# ps_3PS_detect.net
KiCad netlist of a schematic drawn in EAGLE
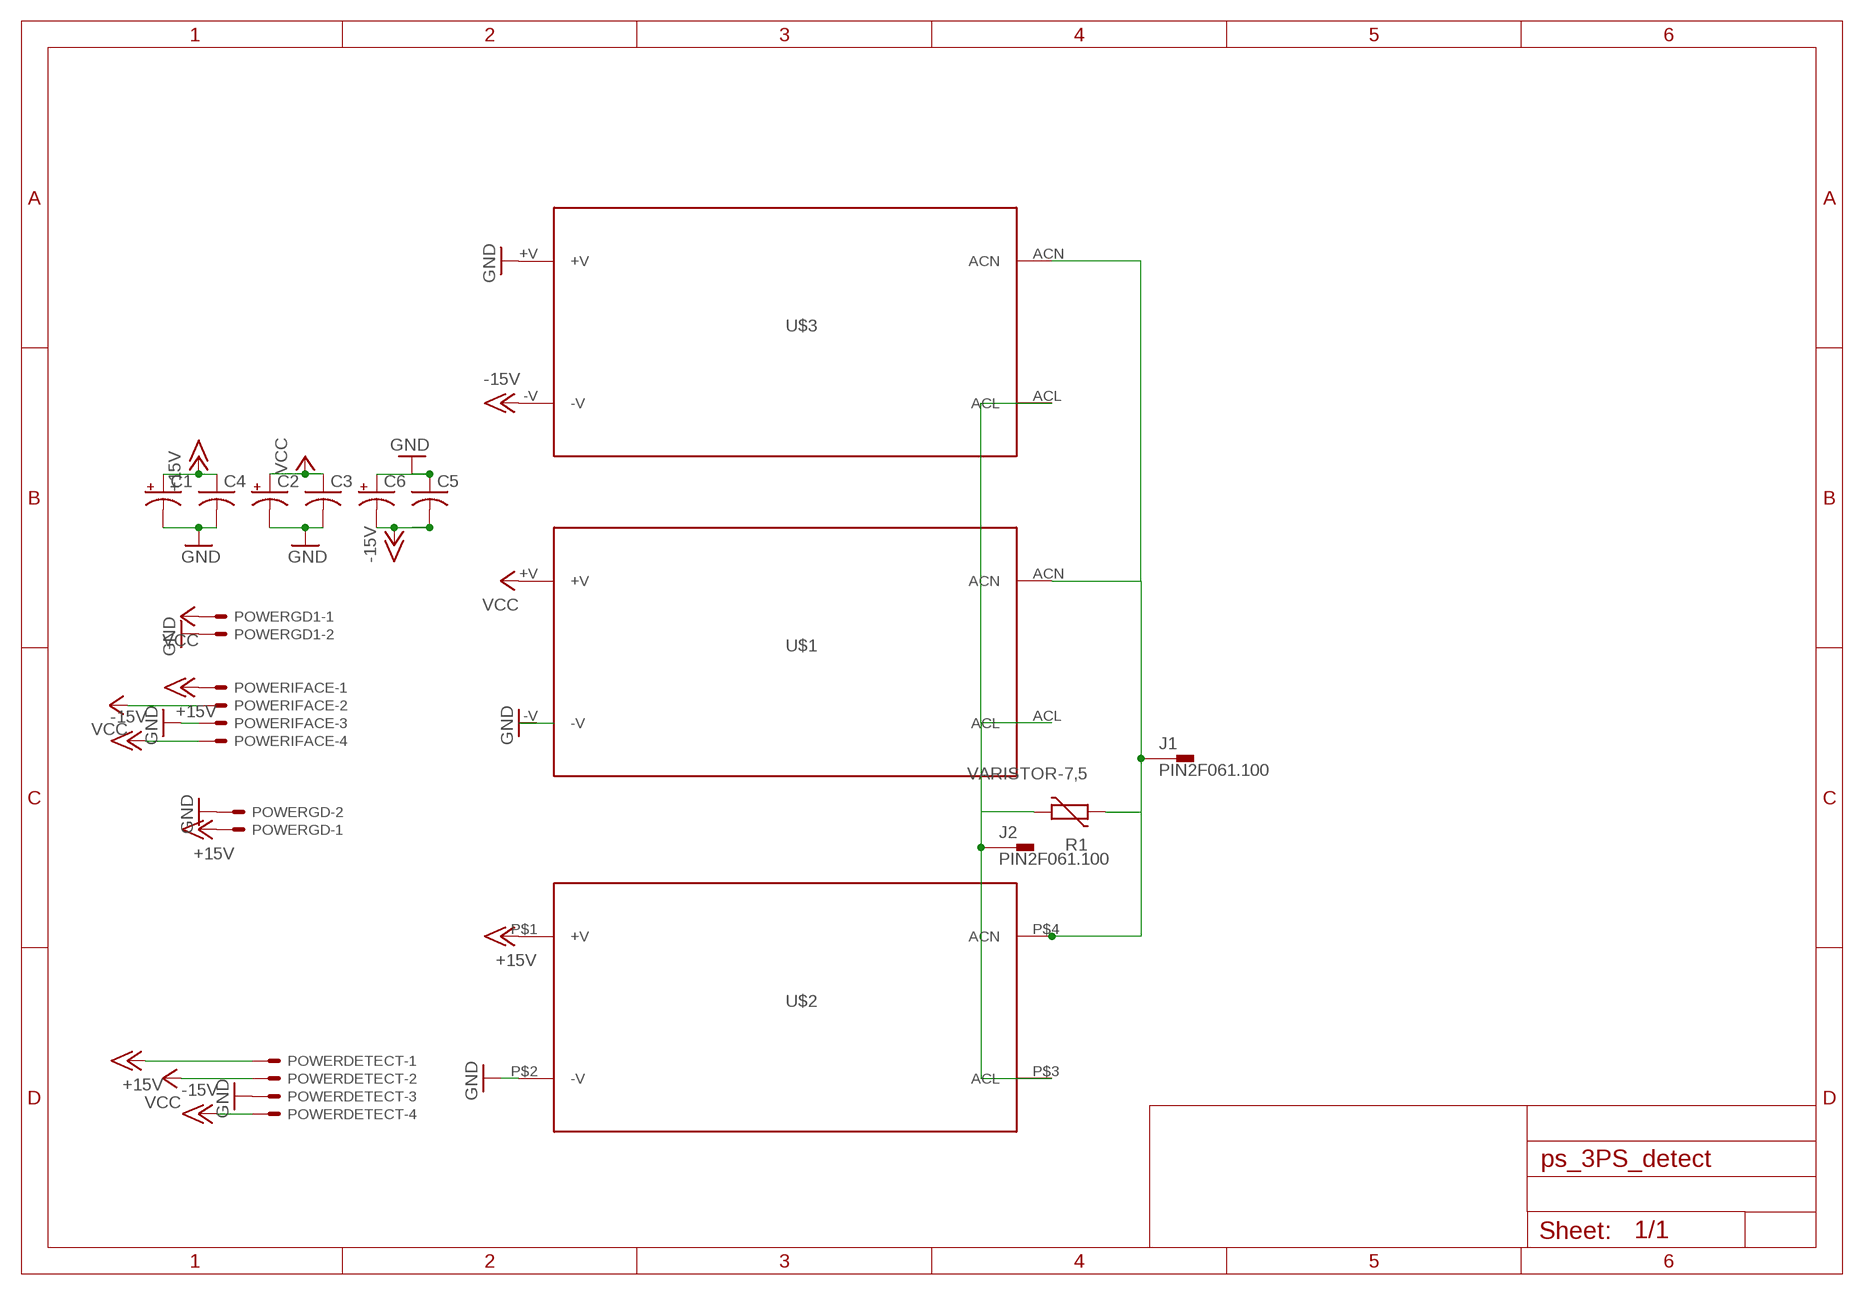
[diagram p0: schematic, sheet 1]

(export (version "E")
  (design (tool "Eeschema 10.0.6"))
  (components
    (comp (ref "C1")
      (value "CPOL-USE5-13")
      (footprint "eagle-import:E5-13")
      (libsource (lib "eagle-import") (part "CPOL-USE5-13"))
    )
    (comp (ref "C2")
      (value "CPOL-USE5-13")
      (footprint "eagle-import:E5-13")
      (libsource (lib "eagle-import") (part "CPOL-USE5-13"))
    )
    (comp (ref "C3")
      (value "C-US050-050X075")
      (footprint "eagle-import:C050-050X075")
      (libsource (lib "eagle-import") (part "C-US050-050X075"))
    )
    (comp (ref "C4")
      (value "C-US050-050X075")
      (footprint "eagle-import:C050-050X075")
      (libsource (lib "eagle-import") (part "C-US050-050X075"))
    )
    (comp (ref "C5")
      (value "C-US050-050X075")
      (footprint "eagle-import:C050-050X075")
      (libsource (lib "eagle-import") (part "C-US050-050X075"))
    )
    (comp (ref "C6")
      (value "CPOL-USE5-13")
      (footprint "eagle-import:E5-13")
      (libsource (lib "eagle-import") (part "CPOL-USE5-13"))
    )
    (comp (ref "J1")
      (value "PIN2F061.100")
      (footprint "eagle-import:F061.100")
      (libsource (lib "eagle-import") (part "PIN2F061.100"))
    )
    (comp (ref "J2")
      (value "PIN2F061.100")
      (footprint "eagle-import:F061.100")
      (libsource (lib "eagle-import") (part "PIN2F061.100"))
    )
    (comp (ref "POWERDETECT")
      (value "KK-156-4")
      (footprint "eagle-import:KK-156-4")
      (libsource (lib "eagle-import") (part "KK-156-4"))
    )
    (comp (ref "POWERGD")
      (value "KK-156-2")
      (footprint "eagle-import:KK-156-2")
      (libsource (lib "eagle-import") (part "KK-156-2"))
    )
    (comp (ref "POWERGD1")
      (value "KK-156-2")
      (footprint "eagle-import:KK-156-2")
      (libsource (lib "eagle-import") (part "KK-156-2"))
    )
    (comp (ref "POWERIFACE")
      (value "KK-156-4")
      (footprint "eagle-import:KK-156-4")
      (libsource (lib "eagle-import") (part "KK-156-4"))
    )
    (comp (ref "R1")
      (value "VARISTOR-7,5")
      (footprint "eagle-import:R-7,5")
      (libsource (lib "eagle-import") (part "VARISTOR-7,5"))
    )
    (comp (ref "U$1")
      (value "IRM-05-05")
      (footprint "eagle-import:IRM-05-05")
      (libsource (lib "eagle-import") (part "IRM-05-05"))
    )
    (comp (ref "U$2")
      (value "IRM-60-12")
      (footprint "eagle-import:IRM-60-12")
      (libsource (lib "eagle-import") (part "IRM-60-12"))
    )
    (comp (ref "U$3")
      (value "IRM-30-15")
      (footprint "eagle-import:IRM-30-15")
      (libsource (lib "eagle-import") (part "IRM-30-15"))
    )
  )
  (nets
    (net (code "1") (name "+15V") (class "Default")
      (node (ref "C1") (pin "+") (pinfunction "+_+") (pintype "passive"))
      (node (ref "C4") (pin "1") (pinfunction "1_1") (pintype "passive"))
      (node (ref "POWERDETECT") (pin "1") (pinfunction "S_1") (pintype "passive"))
      (node (ref "POWERGD") (pin "1") (pinfunction "S_1") (pintype "passive"))
      (node (ref "POWERIFACE") (pin "1") (pinfunction "S_1") (pintype "passive"))
      (node (ref "U$2") (pin "P$1") (pinfunction "+V_P$1") (pintype "bidirectional"))
    )
    (net (code "2") (name "-15V") (class "Default")
      (node (ref "C5") (pin "2") (pinfunction "2_2") (pintype "passive"))
      (node (ref "C6") (pin "-") (pinfunction "-_-") (pintype "passive"))
      (node (ref "POWERDETECT") (pin "4") (pinfunction "S_4") (pintype "passive"))
      (node (ref "POWERIFACE") (pin "4") (pinfunction "S_4") (pintype "passive"))
      (node (ref "U$3") (pin "-V") (pinfunction "-V_-V") (pintype "bidirectional"))
    )
    (net (code "3") (name "GND") (class "Default")
      (node (ref "C1") (pin "-") (pinfunction "-_-") (pintype "passive"))
      (node (ref "C2") (pin "-") (pinfunction "-_-") (pintype "passive"))
      (node (ref "C3") (pin "2") (pinfunction "2_2") (pintype "passive"))
      (node (ref "C4") (pin "2") (pinfunction "2_2") (pintype "passive"))
      (node (ref "C5") (pin "1") (pinfunction "1_1") (pintype "passive"))
      (node (ref "C6") (pin "+") (pinfunction "+_+") (pintype "passive"))
      (node (ref "POWERDETECT") (pin "3") (pinfunction "S_3") (pintype "passive"))
      (node (ref "POWERGD") (pin "2") (pinfunction "S_2") (pintype "passive"))
      (node (ref "POWERGD1") (pin "2") (pinfunction "S_2") (pintype "passive"))
      (node (ref "POWERIFACE") (pin "3") (pinfunction "S_3") (pintype "passive"))
      (node (ref "U$1") (pin "-V") (pinfunction "-V_-V") (pintype "bidirectional"))
      (node (ref "U$2") (pin "P$2") (pinfunction "-V_P$2") (pintype "bidirectional"))
      (node (ref "U$3") (pin "+V") (pinfunction "+V_+V") (pintype "bidirectional"))
    )
    (net (code "4") (name "Net-(U$2-ACL)") (class "Default")
      (node (ref "J2") (pin "A1") (pinfunction "1_A1") (pintype "passive"))
      (node (ref "J2") (pin "A2") (pinfunction "1_A2") (pintype "passive"))
      (node (ref "R1") (pin "1") (pinfunction "1_1") (pintype "passive"))
      (node (ref "U$1") (pin "ACL") (pinfunction "ACL_ACL") (pintype "bidirectional"))
      (node (ref "U$2") (pin "P$3") (pinfunction "ACL_P$3") (pintype "bidirectional"))
      (node (ref "U$3") (pin "ACL") (pinfunction "ACL_ACL") (pintype "bidirectional"))
    )
    (net (code "5") (name "Net-(U$2-ACN)") (class "Default")
      (node (ref "J1") (pin "A1") (pinfunction "1_A1") (pintype "passive"))
      (node (ref "J1") (pin "A2") (pinfunction "1_A2") (pintype "passive"))
      (node (ref "R1") (pin "2") (pinfunction "2_2") (pintype "passive"))
      (node (ref "U$1") (pin "ACN") (pinfunction "ACN_ACN") (pintype "bidirectional"))
      (node (ref "U$2") (pin "P$4") (pinfunction "ACN_P$4") (pintype "bidirectional"))
      (node (ref "U$3") (pin "ACN") (pinfunction "ACN_ACN") (pintype "bidirectional"))
    )
    (net (code "6") (name "VCC") (class "Default")
      (node (ref "C2") (pin "+") (pinfunction "+_+") (pintype "passive"))
      (node (ref "C3") (pin "1") (pinfunction "1_1") (pintype "passive"))
      (node (ref "POWERDETECT") (pin "2") (pinfunction "S_2") (pintype "passive"))
      (node (ref "POWERGD1") (pin "1") (pinfunction "S_1") (pintype "passive"))
      (node (ref "POWERIFACE") (pin "2") (pinfunction "S_2") (pintype "passive"))
      (node (ref "U$1") (pin "+V") (pinfunction "+V_+V") (pintype "bidirectional"))
    )
  )
)
